# class_3_board.net
KiCad netlist of a schematic drawn in EAGLE
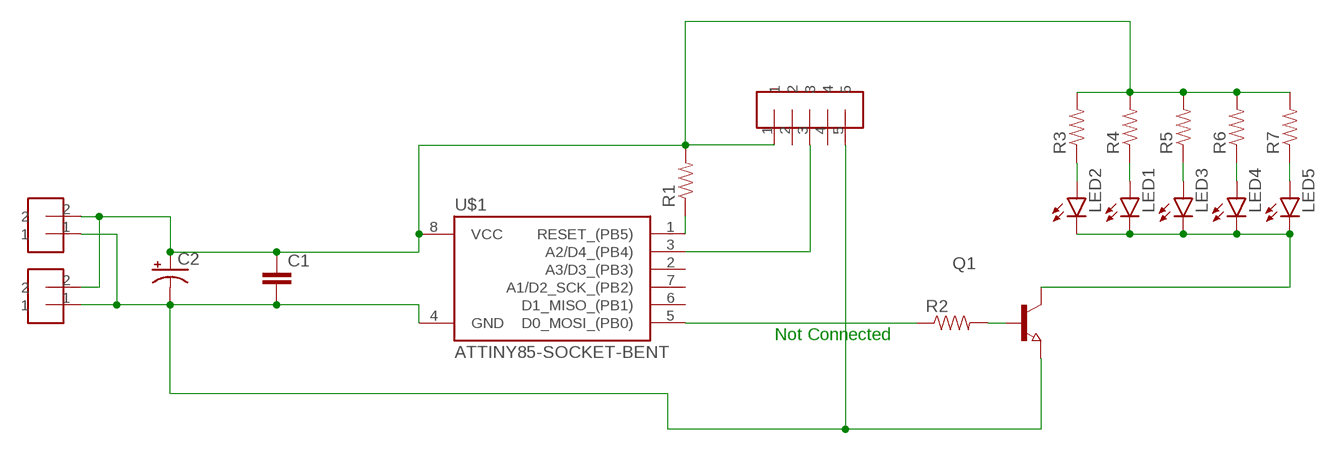
[diagram p0: schematic, sheet 1]

(export (version "E")
  (design (tool "Eeschema 10.0.6"))
  (components
    (comp (ref "C1")
      (value "CAP0603-CAP")
      (footprint "eagle-import:0603-CAP")
      (libsource (lib "eagle-import") (part "CAP0603-CAP"))
    )
    (comp (ref "C2")
      (value "CAP_POLD")
      (footprint "eagle-import:PANASONIC_D")
      (libsource (lib "eagle-import") (part "CAP_POLD"))
    )
    (comp (ref "LED1")
      (value "LED0603")
      (footprint "eagle-import:LED-0603")
      (libsource (lib "eagle-import") (part "LED0603"))
    )
    (comp (ref "LED2")
      (value "LED0603")
      (footprint "eagle-import:LED-0603")
      (libsource (lib "eagle-import") (part "LED0603"))
    )
    (comp (ref "LED3")
      (value "LED0603")
      (footprint "eagle-import:LED-0603")
      (libsource (lib "eagle-import") (part "LED0603"))
    )
    (comp (ref "LED4")
      (value "LED0603")
      (footprint "eagle-import:LED-0603")
      (libsource (lib "eagle-import") (part "LED0603"))
    )
    (comp (ref "LED5")
      (value "LED0603")
      (footprint "eagle-import:LED-0603")
      (libsource (lib "eagle-import") (part "LED0603"))
    )
    (comp (ref "Q1")
      (value "TRANSISTOR-NPN-SOT23")
      (footprint "eagle-import:SOT23")
      (libsource (lib "eagle-import") (part "TRANSISTOR-NPN-SOT23"))
    )
    (comp (ref "R1")
      (value "RESISTOR0603")
      (footprint "eagle-import:0603-RES")
      (libsource (lib "eagle-import") (part "RESISTOR0603"))
    )
    (comp (ref "R2")
      (value "RESISTOR0603")
      (footprint "eagle-import:0603-RES")
      (libsource (lib "eagle-import") (part "RESISTOR0603"))
    )
    (comp (ref "R3")
      (value "RESISTOR0603")
      (footprint "eagle-import:0603-RES")
      (libsource (lib "eagle-import") (part "RESISTOR0603"))
    )
    (comp (ref "R4")
      (value "RESISTOR0603")
      (footprint "eagle-import:0603-RES")
      (libsource (lib "eagle-import") (part "RESISTOR0603"))
    )
    (comp (ref "R5")
      (value "RESISTOR0603")
      (footprint "eagle-import:0603-RES")
      (libsource (lib "eagle-import") (part "RESISTOR0603"))
    )
    (comp (ref "R6")
      (value "RESISTOR0603")
      (footprint "eagle-import:0603-RES")
      (libsource (lib "eagle-import") (part "RESISTOR0603"))
    )
    (comp (ref "R7")
      (value "RESISTOR0603")
      (footprint "eagle-import:0603-RES")
      (libsource (lib "eagle-import") (part "RESISTOR0603"))
    )
    (comp (ref "U$1")
      (value "ATTINY85-SOCKET-BENT")
      (footprint "eagle-import:SOCKET-8PIN-BENT")
      (libsource (lib "eagle-import") (part "ATTINY85-SOCKET-BENT"))
    )
    (comp (ref "U$2")
      (value "HEADER-5")
      (footprint "eagle-import:HEADER-5")
      (libsource (lib "eagle-import") (part "HEADER-5"))
    )
    (comp (ref "U$3")
      (value "HEADER-2")
      (footprint "eagle-import:HEADER-2")
      (libsource (lib "eagle-import") (part "HEADER-2"))
    )
    (comp (ref "U$4")
      (value "HEADER-2")
      (footprint "eagle-import:HEADER-2")
      (libsource (lib "eagle-import") (part "HEADER-2"))
    )
  )
  (nets
    (net (code "1") (name "Net-(LED1-PadA)") (class "Default")
      (node (ref "LED1") (pin "A") (pinfunction "A_A") (pintype "passive"))
      (node (ref "R4") (pin "1") (pinfunction "1_1") (pintype "passive"))
    )
    (net (code "2") (name "Net-(LED2-PadA)") (class "Default")
      (node (ref "LED2") (pin "A") (pinfunction "A_A") (pintype "passive"))
      (node (ref "R3") (pin "1") (pinfunction "1_1") (pintype "passive"))
    )
    (net (code "3") (name "Net-(LED3-PadA)") (class "Default")
      (node (ref "LED3") (pin "A") (pinfunction "A_A") (pintype "passive"))
      (node (ref "R5") (pin "1") (pinfunction "1_1") (pintype "passive"))
    )
    (net (code "4") (name "Net-(LED4-PadA)") (class "Default")
      (node (ref "LED4") (pin "A") (pinfunction "A_A") (pintype "passive"))
      (node (ref "R6") (pin "1") (pinfunction "1_1") (pintype "passive"))
    )
    (net (code "5") (name "Net-(LED5-PadA)") (class "Default")
      (node (ref "LED5") (pin "A") (pinfunction "A_A") (pintype "passive"))
      (node (ref "R7") (pin "1") (pinfunction "1_1") (pintype "passive"))
    )
    (net (code "6") (name "Net-(Q1-B)") (class "Default")
      (node (ref "Q1") (pin "1") (pinfunction "B_1") (pintype "passive"))
      (node (ref "R2") (pin "2") (pinfunction "2_2") (pintype "passive"))
    )
    (net (code "7") (name "Net-(Q1-C)") (class "Default")
      (node (ref "LED1") (pin "C") (pinfunction "C_C") (pintype "passive"))
      (node (ref "LED2") (pin "C") (pinfunction "C_C") (pintype "passive"))
      (node (ref "LED3") (pin "C") (pinfunction "C_C") (pintype "passive"))
      (node (ref "LED4") (pin "C") (pinfunction "C_C") (pintype "passive"))
      (node (ref "LED5") (pin "C") (pinfunction "C_C") (pintype "passive"))
      (node (ref "Q1") (pin "3") (pinfunction "C_3") (pintype "passive"))
    )
    (net (code "8") (name "Net-(Q1-E)") (class "Default")
      (node (ref "C1") (pin "2") (pinfunction "2_2") (pintype "passive"))
      (node (ref "C2") (pin "-") (pinfunction "-_-") (pintype "passive"))
      (node (ref "Q1") (pin "2") (pinfunction "E_2") (pintype "passive"))
      (node (ref "U$1") (pin "4") (pinfunction "GND_4") (pintype "power_in"))
      (node (ref "U$2") (pin "5") (pinfunction "5_5") (pintype "bidirectional"))
      (node (ref "U$3") (pin "1") (pinfunction "1_1") (pintype "bidirectional"))
      (node (ref "U$4") (pin "1") (pinfunction "1_1") (pintype "bidirectional"))
    )
    (net (code "9") (name "Net-(U$1-A2{slash}D4_(PB4))") (class "Default")
      (node (ref "U$1") (pin "3") (pinfunction "A2/D4_(PB4)_3") (pintype "bidirectional"))
      (node (ref "U$2") (pin "3") (pinfunction "3_3") (pintype "bidirectional"))
    )
    (net (code "10") (name "Net-(U$1-D0_MOSI_(PB0))") (class "Default")
      (node (ref "R2") (pin "1") (pinfunction "1_1") (pintype "passive"))
      (node (ref "U$1") (pin "5") (pinfunction "D0_MOSI_(PB0)_5") (pintype "bidirectional"))
    )
    (net (code "11") (name "Net-(U$1-RESET_(PB5))") (class "Default")
      (node (ref "R1") (pin "1") (pinfunction "1_1") (pintype "passive"))
      (node (ref "U$1") (pin "1") (pinfunction "RESET_(PB5)_1") (pintype "bidirectional"))
    )
    (net (code "12") (name "Net-(U$1-VCC)") (class "Default")
      (node (ref "C1") (pin "1") (pinfunction "1_1") (pintype "passive"))
      (node (ref "C2") (pin "+") (pinfunction "+_+") (pintype "passive"))
      (node (ref "R1") (pin "2") (pinfunction "2_2") (pintype "passive"))
      (node (ref "R3") (pin "2") (pinfunction "2_2") (pintype "passive"))
      (node (ref "R4") (pin "2") (pinfunction "2_2") (pintype "passive"))
      (node (ref "R5") (pin "2") (pinfunction "2_2") (pintype "passive"))
      (node (ref "R6") (pin "2") (pinfunction "2_2") (pintype "passive"))
      (node (ref "R7") (pin "2") (pinfunction "2_2") (pintype "passive"))
      (node (ref "U$1") (pin "8") (pinfunction "VCC_8") (pintype "power_in"))
      (node (ref "U$2") (pin "1") (pinfunction "1_1") (pintype "bidirectional"))
      (node (ref "U$3") (pin "2") (pinfunction "2_2") (pintype "bidirectional"))
      (node (ref "U$4") (pin "2") (pinfunction "2_2") (pintype "bidirectional"))
    )
    (net (code "13") (name "unconnected-(U$1-A1{slash}D2_SCK_(PB2)-Pad7)") (class "Default")
      (node (ref "U$1") (pin "7") (pinfunction "A1/D2_SCK_(PB2)_7") (pintype "bidirectional"))
    )
    (net (code "14") (name "unconnected-(U$1-A3{slash}D3_(PB3)-Pad2)") (class "Default")
      (node (ref "U$1") (pin "2") (pinfunction "A3/D3_(PB3)_2") (pintype "bidirectional"))
    )
    (net (code "15") (name "unconnected-(U$1-D1_MISO_(PB1)-Pad6)") (class "Default")
      (node (ref "U$1") (pin "6") (pinfunction "D1_MISO_(PB1)_6") (pintype "bidirectional"))
    )
    (net (code "16") (name "unconnected-(U$2-Pad2)") (class "Default")
      (node (ref "U$2") (pin "2") (pinfunction "2_2") (pintype "bidirectional"))
    )
    (net (code "17") (name "unconnected-(U$2-Pad4)") (class "Default")
      (node (ref "U$2") (pin "4") (pinfunction "4_4") (pintype "bidirectional"))
    )
  )
)
